# McPiFace-Aerial-V1.net
KiCad netlist of a schematic drawn in EAGLE
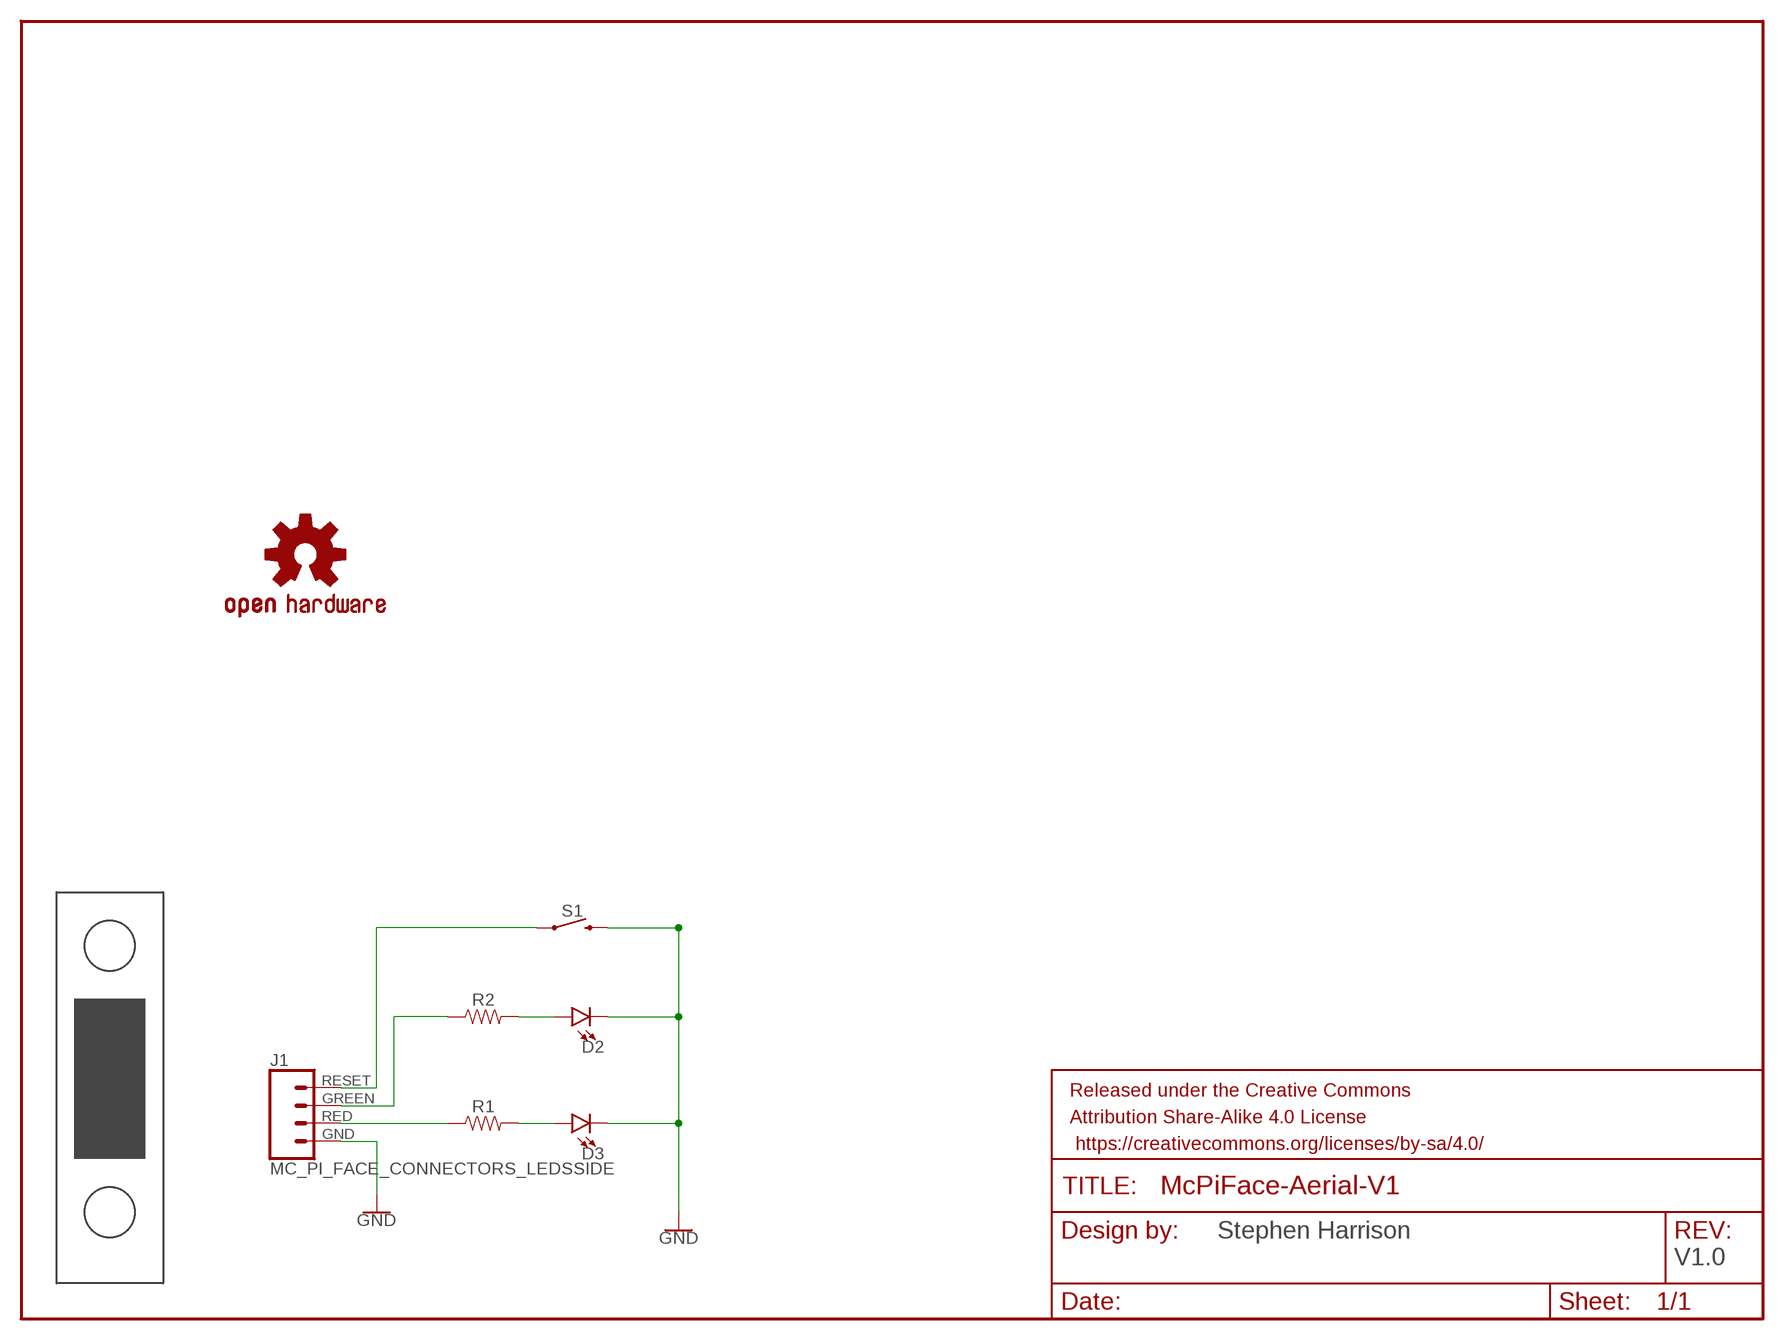
[diagram p0: schematic, sheet 1]

(export (version "E")
  (design (tool "Eeschema 10.0.6"))
  (components
    (comp (ref "D2")
      (value "LEDLED-1206-BOTTOM-2.0MM-GREEN")
      (footprint "eagle-import:LED-1206-BOTTOM-2.0MM")
      (libsource (lib "eagle-import") (part "LEDLED-1206-BOTTOM-2.0MM-GREEN"))
    )
    (comp (ref "D3")
      (value "LEDLED-1206-BOTTOM-2.0MM-RED")
      (footprint "eagle-import:LED-1206-BOTTOM-2.0MM")
      (libsource (lib "eagle-import") (part "LEDLED-1206-BOTTOM-2.0MM-RED"))
    )
    (comp (ref "FRAME1")
      (value "FRAME-LETTER")
      (footprint "eagle-import:CREATIVE_COMMONS")
      (libsource (lib "eagle-import") (part "FRAME-LETTER"))
    )
    (comp (ref "J1")
      (value "MC_PI_FACE_CONNECTORS_LEDSSIDE")
      (footprint "eagle-import:JST-4-SH-1.0MM-SIDE")
      (fields (field (name "MFG") "SM04B-SRSS-TB(LF)(SN)"))
      (libsource (lib "eagle-import") (part "MC_PI_FACE_CONNECTORS_LEDSSIDE"))
    )
    (comp (ref "LOGO1")
      (value "OSHW-LOGOL")
      (footprint "eagle-import:OSHW-LOGO-L")
      (libsource (lib "eagle-import") (part "OSHW-LOGOL"))
    )
    (comp (ref "R1")
      (value "RESISTOR0805")
      (footprint "eagle-import:0805")
      (libsource (lib "eagle-import") (part "RESISTOR0805"))
    )
    (comp (ref "R2")
      (value "RESISTOR0805")
      (footprint "eagle-import:0805")
      (libsource (lib "eagle-import") (part "RESISTOR0805"))
    )
    (comp (ref "S1")
      (value "MOMENTARY-SWITCH-SPSTTACKTILE_SWITCH_PTH_6.0MM_NO_TOP_RESIST")
      (footprint "eagle-import:TACTILE_SWITCH_PTH_6.0MM_NO_TOP_RESIST")
      (libsource (lib "eagle-import") (part "MOMENTARY-SWITCH-SPSTTACKTILE_SWITCH_PTH_6.0MM_NO_TOP_RESIST"))
    )
    (comp (ref "U$1")
      (value "MC_PI_FACE_PANELDOUBLE")
      (footprint "eagle-import:MC_PI_DOUBLE_FACE")
      (libsource (lib "eagle-import") (part "MC_PI_FACE_PANELDOUBLE"))
    )
  )
  (nets
    (net (code "1") (name "GND") (class "Default")
      (node (ref "D2") (pin "C") (pinfunction "C_C") (pintype "passive"))
      (node (ref "D3") (pin "C") (pinfunction "C_C") (pintype "passive"))
      (node (ref "J1") (pin "GND") (pinfunction "GND_GND") (pintype "power_in"))
      (node (ref "S1") (pin "3") (pinfunction "2_3") (pintype "passive"))
    )
    (net (code "2") (name "Net-(D2-PadA)") (class "Default")
      (node (ref "D2") (pin "A") (pinfunction "A_A") (pintype "passive"))
      (node (ref "R2") (pin "2") (pinfunction "2_2") (pintype "passive"))
    )
    (net (code "3") (name "Net-(D3-PadA)") (class "Default")
      (node (ref "D3") (pin "A") (pinfunction "A_A") (pintype "passive"))
      (node (ref "R1") (pin "2") (pinfunction "2_2") (pintype "passive"))
    )
    (net (code "4") (name "Net-(J1-PadGREEN)") (class "Default")
      (node (ref "J1") (pin "GREEN") (pinfunction "GREEN_GREEN") (pintype "passive"))
      (node (ref "R2") (pin "1") (pinfunction "1_1") (pintype "passive"))
    )
    (net (code "5") (name "Net-(J1-PadRED)") (class "Default")
      (node (ref "J1") (pin "RED") (pinfunction "RED_RED") (pintype "passive"))
      (node (ref "R1") (pin "1") (pinfunction "1_1") (pintype "passive"))
    )
    (net (code "6") (name "Net-(J1-PadRESET)") (class "Default")
      (node (ref "J1") (pin "RESET") (pinfunction "RESET_RESET") (pintype "passive"))
      (node (ref "S1") (pin "1") (pinfunction "1_1") (pintype "passive"))
    )
  )
)
